# A6BPSLD-3.net
KiCad netlist of a schematic drawn in EAGLE
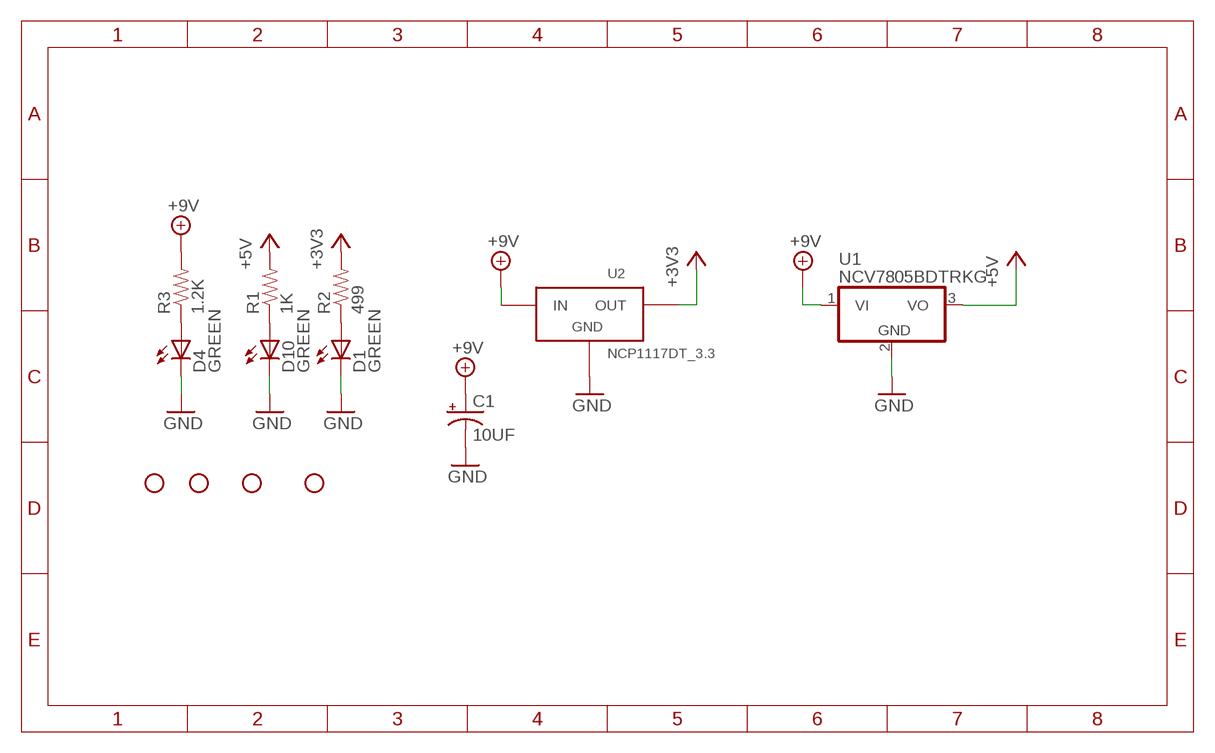
[diagram p0: schematic, sheet 1]
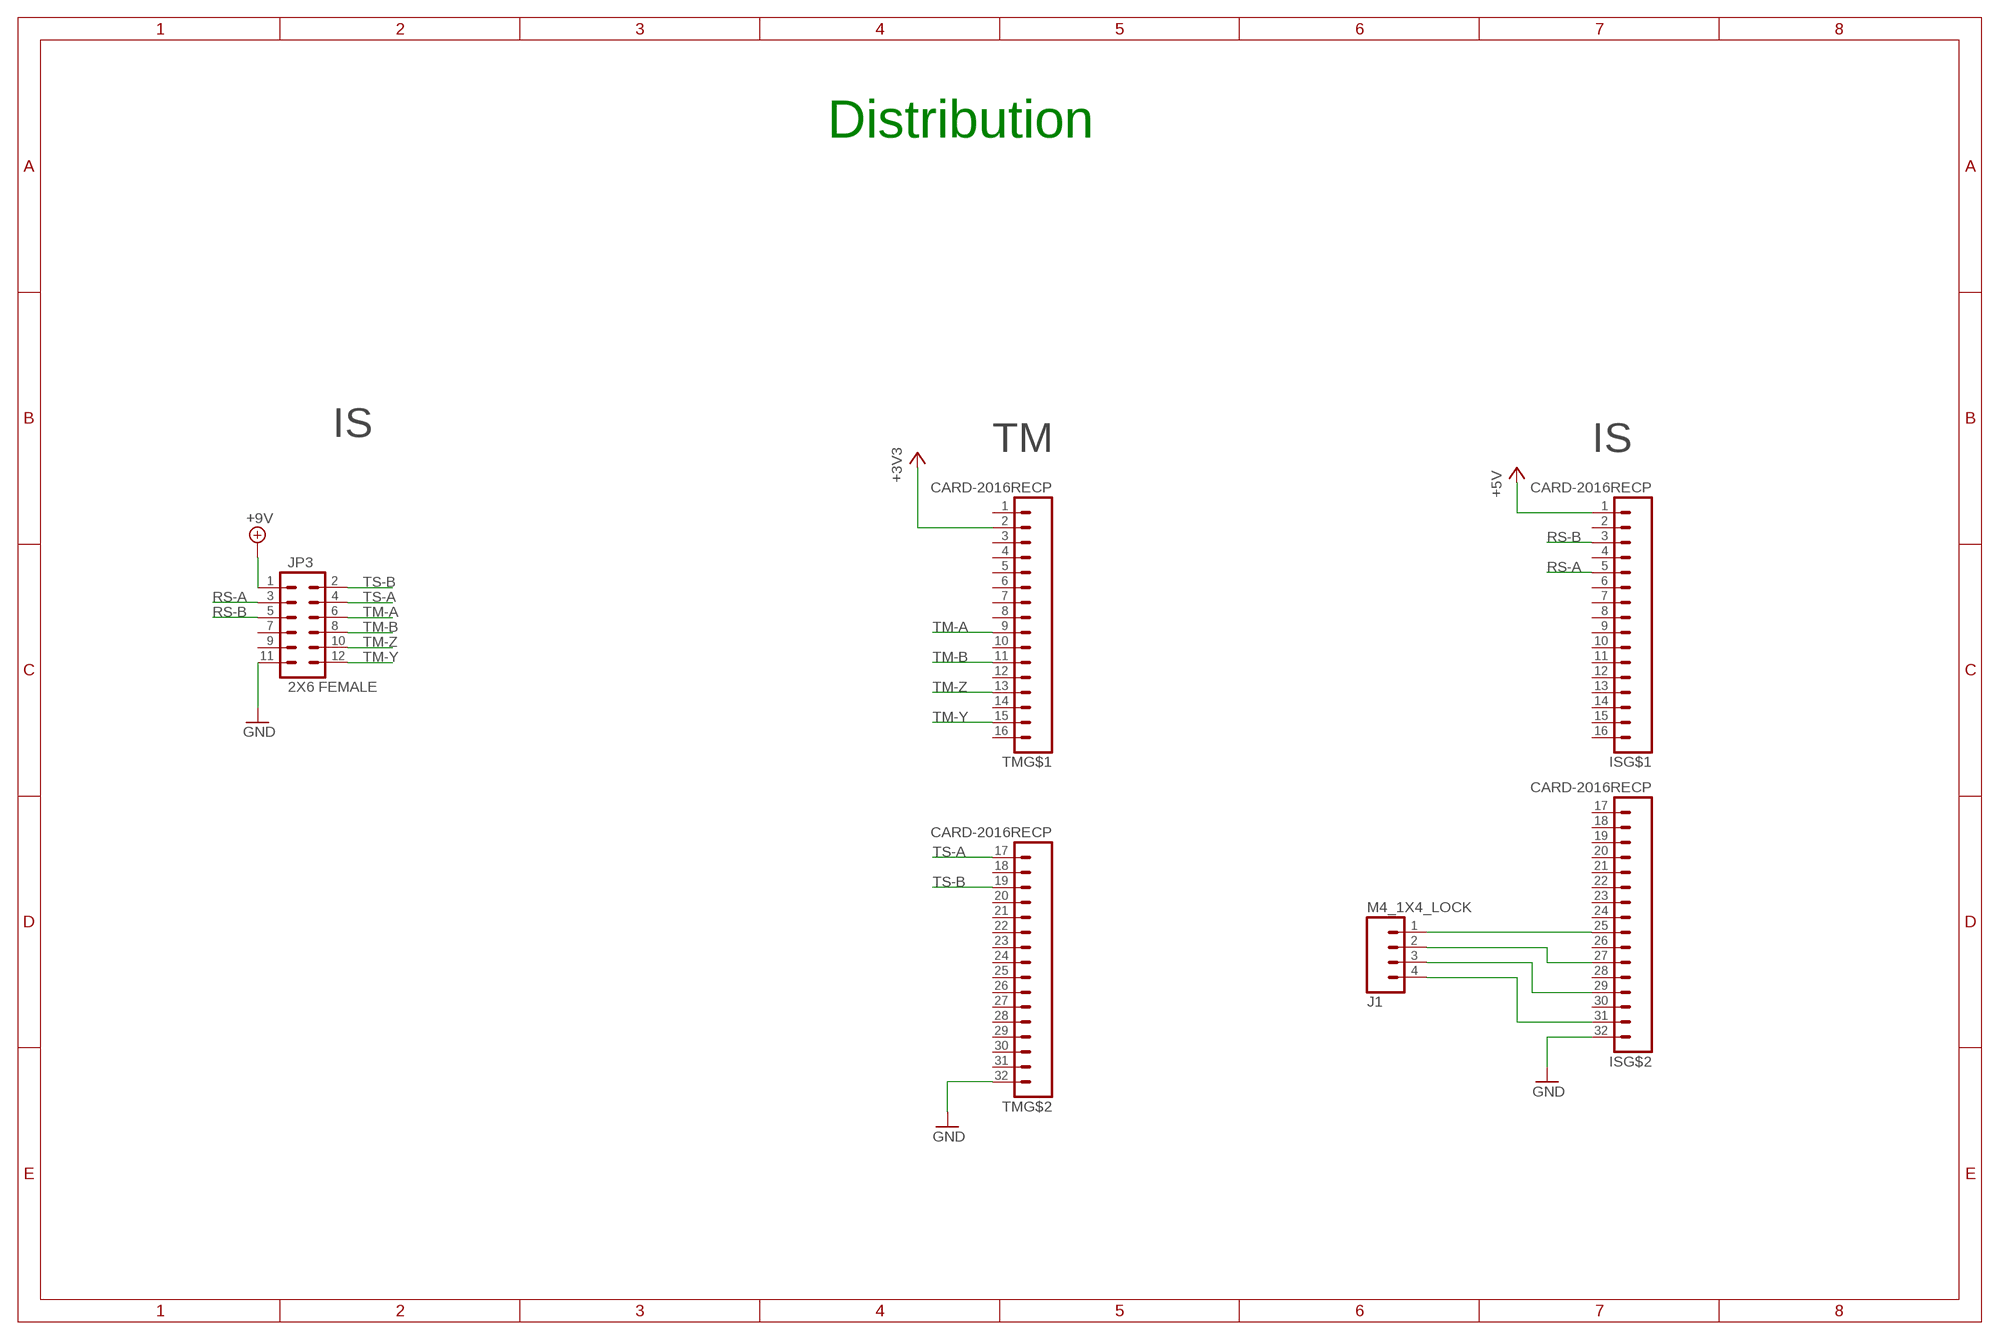
[diagram p1: schematic, sheet 2]

(export (version "E")
  (design (tool "Eeschema 10.0.6"))
  (components
    (comp (ref "C1")
      (value "10UF")
      (footprint "eagle-import:EIA3216-16V")
      (fields (field (name "PARTNO") "T491A106M016AT"))
      (libsource (lib "eagle-import") (part "CAP-POL_10UF_16V"))
    )
    (comp (ref "D1")
      (value "GREEN")
      (footprint "eagle-import:CHIP_LED0805")
      (fields (field (name "PARTNO") "LTST-S220GKT"))
      (libsource (lib "eagle-import") (part "LED_GREEN"))
    )
    (comp (ref "D4")
      (value "GREEN")
      (footprint "eagle-import:CHIP_LED0805")
      (fields (field (name "PARTNO") "LTST-S220GKT"))
      (libsource (lib "eagle-import") (part "LED_GREEN"))
    )
    (comp (ref "D10")
      (value "GREEN")
      (footprint "eagle-import:CHIP_LED0805")
      (fields (field (name "PARTNO") "LTST-S220GKT"))
      (libsource (lib "eagle-import") (part "LED_GREEN"))
    )
    (comp (ref "R1")
      (value "1K")
      (footprint "eagle-import:0805")
      (fields (field (name "PARTNO") "RC0805FR-071KL"))
      (libsource (lib "eagle-import") (part "RES_1K_1%_0805"))
    )
    (comp (ref "R2")
      (value "499")
      (footprint "eagle-import:0805")
      (fields (field (name "PARTNO") "RC0805FR-07499RL"))
      (libsource (lib "eagle-import") (part "RES_499_1%_0805"))
    )
    (comp (ref "R3")
      (value "1.2K")
      (footprint "eagle-import:0805")
      (fields (field (name "PARTNO") "RC0805FR-071K2L"))
      (libsource (lib "eagle-import") (part "RES_1.2K_1%_0805"))
    )
    (comp (ref "STANDOFF2")
      (value "STAND-OFF")
      (footprint "eagle-import:STAND-OFF")
      (libsource (lib "eagle-import") (part "STAND-OFF"))
    )
    (comp (ref "STANDOFF6")
      (value "STAND-OFF")
      (footprint "eagle-import:STAND-OFF")
      (libsource (lib "eagle-import") (part "STAND-OFF"))
    )
    (comp (ref "STANDOFF7")
      (value "STAND-OFF")
      (footprint "eagle-import:STAND-OFF")
      (libsource (lib "eagle-import") (part "STAND-OFF"))
    )
    (comp (ref "STANDOFF8")
      (value "STAND-OFF")
      (footprint "eagle-import:STAND-OFF")
      (libsource (lib "eagle-import") (part "STAND-OFF"))
    )
    (comp (ref "U1")
      (value "NCV7805BDTRKG")
      (footprint "eagle-import:DPAK")
      (libsource (lib "eagle-import") (part "NCV7805BDTRKG"))
    )
    (comp (ref "U2")
      (value "NCP1117DT_3.3")
      (footprint "eagle-import:DPAK")
      (fields (field (name "PARTNO") "NCP1117DT33RKG"))
      (libsource (lib "eagle-import") (part "NCP1117DT_3.3"))
    )
    (comp (ref "IS")
      (value "CARD-2016RECP")
      (footprint "eagle-import:CARD-2016-RCP")
      (libsource (lib "eagle-import") (part "CARD-2016RECP"))
    )
    (comp (ref "J1")
      (value "M4_1X4_LOCK")
      (footprint "eagle-import:MOLEX_1X4")
      (fields (field (name "PARTNO") "0022232041"))
      (libsource (lib "eagle-import") (part "M4_1X4_LOCK"))
    )
    (comp (ref "JP3")
      (value "2X6 FEMALE")
      (footprint "eagle-import:2X6")
      (libsource (lib "eagle-import") (part "M06X2PTH_FEMALE"))
    )
    (comp (ref "TM")
      (value "CARD-2016RECP")
      (footprint "eagle-import:CARD-2016-RCP")
      (libsource (lib "eagle-import") (part "CARD-2016RECP"))
    )
  )
  (nets
    (net (code "1") (name "+3V3") (class "Default")
      (node (ref "R2") (pin "2") (pinfunction "2_2") (pintype "passive"))
      (node (ref "TM") (pin "2") (pinfunction "2_2") (pintype "passive"))
      (node (ref "U2") (pin "2") (pinfunction "OUT_2") (pintype "bidirectional"))
    )
    (net (code "2") (name "+5V") (class "Default")
      (node (ref "IS") (pin "1") (pinfunction "1_1") (pintype "passive"))
      (node (ref "R1") (pin "2") (pinfunction "2_2") (pintype "passive"))
      (node (ref "U1") (pin "3") (pinfunction "VO_3") (pintype "passive"))
    )
    (net (code "3") (name "+9V") (class "Default")
      (node (ref "C1") (pin "A") (pinfunction "+_A") (pintype "passive"))
      (node (ref "JP3") (pin "1") (pinfunction "1_1") (pintype "passive"))
      (node (ref "R3") (pin "2") (pinfunction "2_2") (pintype "passive"))
      (node (ref "U1") (pin "1") (pinfunction "VI_1") (pintype "input"))
      (node (ref "U2") (pin "3") (pinfunction "IN_3") (pintype "bidirectional"))
    )
    (net (code "4") (name "GND") (class "Default")
      (node (ref "C1") (pin "C") (pinfunction "-_C") (pintype "passive"))
      (node (ref "D1") (pin "C") (pinfunction "C_C") (pintype "passive"))
      (node (ref "D10") (pin "C") (pinfunction "C_C") (pintype "passive"))
      (node (ref "D4") (pin "C") (pinfunction "C_C") (pintype "passive"))
      (node (ref "IS") (pin "32") (pinfunction "16_32") (pintype "passive"))
      (node (ref "JP3") (pin "11") (pinfunction "11_11") (pintype "passive"))
      (node (ref "TM") (pin "32") (pinfunction "16_32") (pintype "passive"))
      (node (ref "U1") (pin "2") (pinfunction "GND_2") (pintype "passive"))
      (node (ref "U2") (pin "1") (pinfunction "GND_1") (pintype "bidirectional"))
    )
    (net (code "5") (name "Net-(D1-PadA)") (class "Default")
      (node (ref "D1") (pin "A") (pinfunction "A_A") (pintype "passive"))
      (node (ref "R2") (pin "1") (pinfunction "1_1") (pintype "passive"))
    )
    (net (code "6") (name "Net-(D4-PadA)") (class "Default")
      (node (ref "D4") (pin "A") (pinfunction "A_A") (pintype "passive"))
      (node (ref "R3") (pin "1") (pinfunction "1_1") (pintype "passive"))
    )
    (net (code "7") (name "Net-(D10-PadA)") (class "Default")
      (node (ref "D10") (pin "A") (pinfunction "A_A") (pintype "passive"))
      (node (ref "R1") (pin "1") (pinfunction "1_1") (pintype "passive"))
    )
    (net (code "8") (name "Net-(ISB-9)") (class "Default")
      (node (ref "IS") (pin "25") (pinfunction "9_25") (pintype "passive"))
      (node (ref "J1") (pin "1") (pinfunction "1_1") (pintype "passive"))
    )
    (net (code "9") (name "Net-(ISB-11)") (class "Default")
      (node (ref "IS") (pin "27") (pinfunction "11_27") (pintype "passive"))
      (node (ref "J1") (pin "2") (pinfunction "2_2") (pintype "passive"))
    )
    (net (code "10") (name "Net-(ISB-13)") (class "Default")
      (node (ref "IS") (pin "29") (pinfunction "13_29") (pintype "passive"))
      (node (ref "J1") (pin "3") (pinfunction "3_3") (pintype "passive"))
    )
    (net (code "11") (name "Net-(ISB-15)") (class "Default")
      (node (ref "IS") (pin "31") (pinfunction "15_31") (pintype "passive"))
      (node (ref "J1") (pin "4") (pinfunction "4_4") (pintype "passive"))
    )
    (net (code "12") (name "RS-A") (class "Default")
      (node (ref "IS") (pin "5") (pinfunction "5_5") (pintype "passive"))
      (node (ref "JP3") (pin "3") (pinfunction "3_3") (pintype "passive"))
    )
    (net (code "13") (name "RS-B") (class "Default")
      (node (ref "IS") (pin "3") (pinfunction "3_3") (pintype "passive"))
      (node (ref "JP3") (pin "5") (pinfunction "5_5") (pintype "passive"))
    )
    (net (code "14") (name "TM-A") (class "Default")
      (node (ref "JP3") (pin "6") (pinfunction "6_6") (pintype "passive"))
      (node (ref "TM") (pin "9") (pinfunction "9_9") (pintype "passive"))
    )
    (net (code "15") (name "TM-B") (class "Default")
      (node (ref "JP3") (pin "8") (pinfunction "8_8") (pintype "passive"))
      (node (ref "TM") (pin "11") (pinfunction "11_11") (pintype "passive"))
    )
    (net (code "16") (name "TM-Y") (class "Default")
      (node (ref "JP3") (pin "12") (pinfunction "12_12") (pintype "passive"))
      (node (ref "TM") (pin "15") (pinfunction "15_15") (pintype "passive"))
    )
    (net (code "17") (name "TM-Z") (class "Default")
      (node (ref "JP3") (pin "10") (pinfunction "10_10") (pintype "passive"))
      (node (ref "TM") (pin "13") (pinfunction "13_13") (pintype "passive"))
    )
    (net (code "18") (name "TS-A") (class "Default")
      (node (ref "JP3") (pin "4") (pinfunction "4_4") (pintype "passive"))
      (node (ref "TM") (pin "17") (pinfunction "1_17") (pintype "passive"))
    )
    (net (code "19") (name "TS-B") (class "Default")
      (node (ref "JP3") (pin "2") (pinfunction "2_2") (pintype "passive"))
      (node (ref "TM") (pin "19") (pinfunction "3_19") (pintype "passive"))
    )
    (net (code "20") (name "unconnected-(IS-Pad2)") (class "Default")
      (node (ref "IS") (pin "2") (pinfunction "2_2") (pintype "passive"))
    )
    (net (code "21") (name "unconnected-(IS-Pad4)") (class "Default")
      (node (ref "IS") (pin "4") (pinfunction "4_4") (pintype "passive"))
    )
    (net (code "22") (name "unconnected-(IS-Pad6)") (class "Default")
      (node (ref "IS") (pin "6") (pinfunction "6_6") (pintype "passive"))
    )
    (net (code "23") (name "unconnected-(IS-Pad7)") (class "Default")
      (node (ref "IS") (pin "7") (pinfunction "7_7") (pintype "passive"))
    )
    (net (code "24") (name "unconnected-(IS-Pad8)") (class "Default")
      (node (ref "IS") (pin "8") (pinfunction "8_8") (pintype "passive"))
    )
    (net (code "25") (name "unconnected-(IS-Pad9)") (class "Default")
      (node (ref "IS") (pin "9") (pinfunction "9_9") (pintype "passive"))
    )
    (net (code "26") (name "unconnected-(IS-Pad10)") (class "Default")
      (node (ref "IS") (pin "10") (pinfunction "10_10") (pintype "passive"))
    )
    (net (code "27") (name "unconnected-(IS-Pad11)") (class "Default")
      (node (ref "IS") (pin "11") (pinfunction "11_11") (pintype "passive"))
    )
    (net (code "28") (name "unconnected-(IS-Pad12)") (class "Default")
      (node (ref "IS") (pin "12") (pinfunction "12_12") (pintype "passive"))
    )
    (net (code "29") (name "unconnected-(IS-Pad13)") (class "Default")
      (node (ref "IS") (pin "13") (pinfunction "13_13") (pintype "passive"))
    )
    (net (code "30") (name "unconnected-(IS-Pad14)") (class "Default")
      (node (ref "IS") (pin "14") (pinfunction "14_14") (pintype "passive"))
    )
    (net (code "31") (name "unconnected-(IS-Pad15)") (class "Default")
      (node (ref "IS") (pin "15") (pinfunction "15_15") (pintype "passive"))
    )
    (net (code "32") (name "unconnected-(IS-Pad16)") (class "Default")
      (node (ref "IS") (pin "16") (pinfunction "16_16") (pintype "passive"))
    )
    (net (code "33") (name "unconnected-(ISB-1-Pad17)") (class "Default")
      (node (ref "IS") (pin "17") (pinfunction "1_17") (pintype "passive"))
    )
    (net (code "34") (name "unconnected-(ISB-2-Pad18)") (class "Default")
      (node (ref "IS") (pin "18") (pinfunction "2_18") (pintype "passive"))
    )
    (net (code "35") (name "unconnected-(ISB-3-Pad19)") (class "Default")
      (node (ref "IS") (pin "19") (pinfunction "3_19") (pintype "passive"))
    )
    (net (code "36") (name "unconnected-(ISB-4-Pad20)") (class "Default")
      (node (ref "IS") (pin "20") (pinfunction "4_20") (pintype "passive"))
    )
    (net (code "37") (name "unconnected-(ISB-5-Pad21)") (class "Default")
      (node (ref "IS") (pin "21") (pinfunction "5_21") (pintype "passive"))
    )
    (net (code "38") (name "unconnected-(ISB-6-Pad22)") (class "Default")
      (node (ref "IS") (pin "22") (pinfunction "6_22") (pintype "passive"))
    )
    (net (code "39") (name "unconnected-(ISB-7-Pad23)") (class "Default")
      (node (ref "IS") (pin "23") (pinfunction "7_23") (pintype "passive"))
    )
    (net (code "40") (name "unconnected-(ISB-8-Pad24)") (class "Default")
      (node (ref "IS") (pin "24") (pinfunction "8_24") (pintype "passive"))
    )
    (net (code "41") (name "unconnected-(ISB-10-Pad26)") (class "Default")
      (node (ref "IS") (pin "26") (pinfunction "10_26") (pintype "passive"))
    )
    (net (code "42") (name "unconnected-(ISB-12-Pad28)") (class "Default")
      (node (ref "IS") (pin "28") (pinfunction "12_28") (pintype "passive"))
    )
    (net (code "43") (name "unconnected-(ISB-14-Pad30)") (class "Default")
      (node (ref "IS") (pin "30") (pinfunction "14_30") (pintype "passive"))
    )
    (net (code "44") (name "unconnected-(JP3-Pad7)") (class "Default")
      (node (ref "JP3") (pin "7") (pinfunction "7_7") (pintype "passive"))
    )
    (net (code "45") (name "unconnected-(JP3-Pad9)") (class "Default")
      (node (ref "JP3") (pin "9") (pinfunction "9_9") (pintype "passive"))
    )
    (net (code "46") (name "unconnected-(TM-Pad1)") (class "Default")
      (node (ref "TM") (pin "1") (pinfunction "1_1") (pintype "passive"))
    )
    (net (code "47") (name "unconnected-(TM-Pad3)") (class "Default")
      (node (ref "TM") (pin "3") (pinfunction "3_3") (pintype "passive"))
    )
    (net (code "48") (name "unconnected-(TM-Pad4)") (class "Default")
      (node (ref "TM") (pin "4") (pinfunction "4_4") (pintype "passive"))
    )
    (net (code "49") (name "unconnected-(TM-Pad5)") (class "Default")
      (node (ref "TM") (pin "5") (pinfunction "5_5") (pintype "passive"))
    )
    (net (code "50") (name "unconnected-(TM-Pad6)") (class "Default")
      (node (ref "TM") (pin "6") (pinfunction "6_6") (pintype "passive"))
    )
    (net (code "51") (name "unconnected-(TM-Pad7)") (class "Default")
      (node (ref "TM") (pin "7") (pinfunction "7_7") (pintype "passive"))
    )
    (net (code "52") (name "unconnected-(TM-Pad8)") (class "Default")
      (node (ref "TM") (pin "8") (pinfunction "8_8") (pintype "passive"))
    )
    (net (code "53") (name "unconnected-(TM-Pad10)") (class "Default")
      (node (ref "TM") (pin "10") (pinfunction "10_10") (pintype "passive"))
    )
    (net (code "54") (name "unconnected-(TM-Pad12)") (class "Default")
      (node (ref "TM") (pin "12") (pinfunction "12_12") (pintype "passive"))
    )
    (net (code "55") (name "unconnected-(TM-Pad14)") (class "Default")
      (node (ref "TM") (pin "14") (pinfunction "14_14") (pintype "passive"))
    )
    (net (code "56") (name "unconnected-(TM-Pad16)") (class "Default")
      (node (ref "TM") (pin "16") (pinfunction "16_16") (pintype "passive"))
    )
    (net (code "57") (name "unconnected-(TMB-2-Pad18)") (class "Default")
      (node (ref "TM") (pin "18") (pinfunction "2_18") (pintype "passive"))
    )
    (net (code "58") (name "unconnected-(TMB-4-Pad20)") (class "Default")
      (node (ref "TM") (pin "20") (pinfunction "4_20") (pintype "passive"))
    )
    (net (code "59") (name "unconnected-(TMB-5-Pad21)") (class "Default")
      (node (ref "TM") (pin "21") (pinfunction "5_21") (pintype "passive"))
    )
    (net (code "60") (name "unconnected-(TMB-6-Pad22)") (class "Default")
      (node (ref "TM") (pin "22") (pinfunction "6_22") (pintype "passive"))
    )
    (net (code "61") (name "unconnected-(TMB-7-Pad23)") (class "Default")
      (node (ref "TM") (pin "23") (pinfunction "7_23") (pintype "passive"))
    )
    (net (code "62") (name "unconnected-(TMB-8-Pad24)") (class "Default")
      (node (ref "TM") (pin "24") (pinfunction "8_24") (pintype "passive"))
    )
    (net (code "63") (name "unconnected-(TMB-9-Pad25)") (class "Default")
      (node (ref "TM") (pin "25") (pinfunction "9_25") (pintype "passive"))
    )
    (net (code "64") (name "unconnected-(TMB-10-Pad26)") (class "Default")
      (node (ref "TM") (pin "26") (pinfunction "10_26") (pintype "passive"))
    )
    (net (code "65") (name "unconnected-(TMB-11-Pad27)") (class "Default")
      (node (ref "TM") (pin "27") (pinfunction "11_27") (pintype "passive"))
    )
    (net (code "66") (name "unconnected-(TMB-12-Pad28)") (class "Default")
      (node (ref "TM") (pin "28") (pinfunction "12_28") (pintype "passive"))
    )
    (net (code "67") (name "unconnected-(TMB-13-Pad29)") (class "Default")
      (node (ref "TM") (pin "29") (pinfunction "13_29") (pintype "passive"))
    )
    (net (code "68") (name "unconnected-(TMB-14-Pad30)") (class "Default")
      (node (ref "TM") (pin "30") (pinfunction "14_30") (pintype "passive"))
    )
    (net (code "69") (name "unconnected-(TMB-15-Pad31)") (class "Default")
      (node (ref "TM") (pin "31") (pinfunction "15_31") (pintype "passive"))
    )
  )
)
